# MainPower.net
KiCad netlist of a schematic drawn in Altium Designer
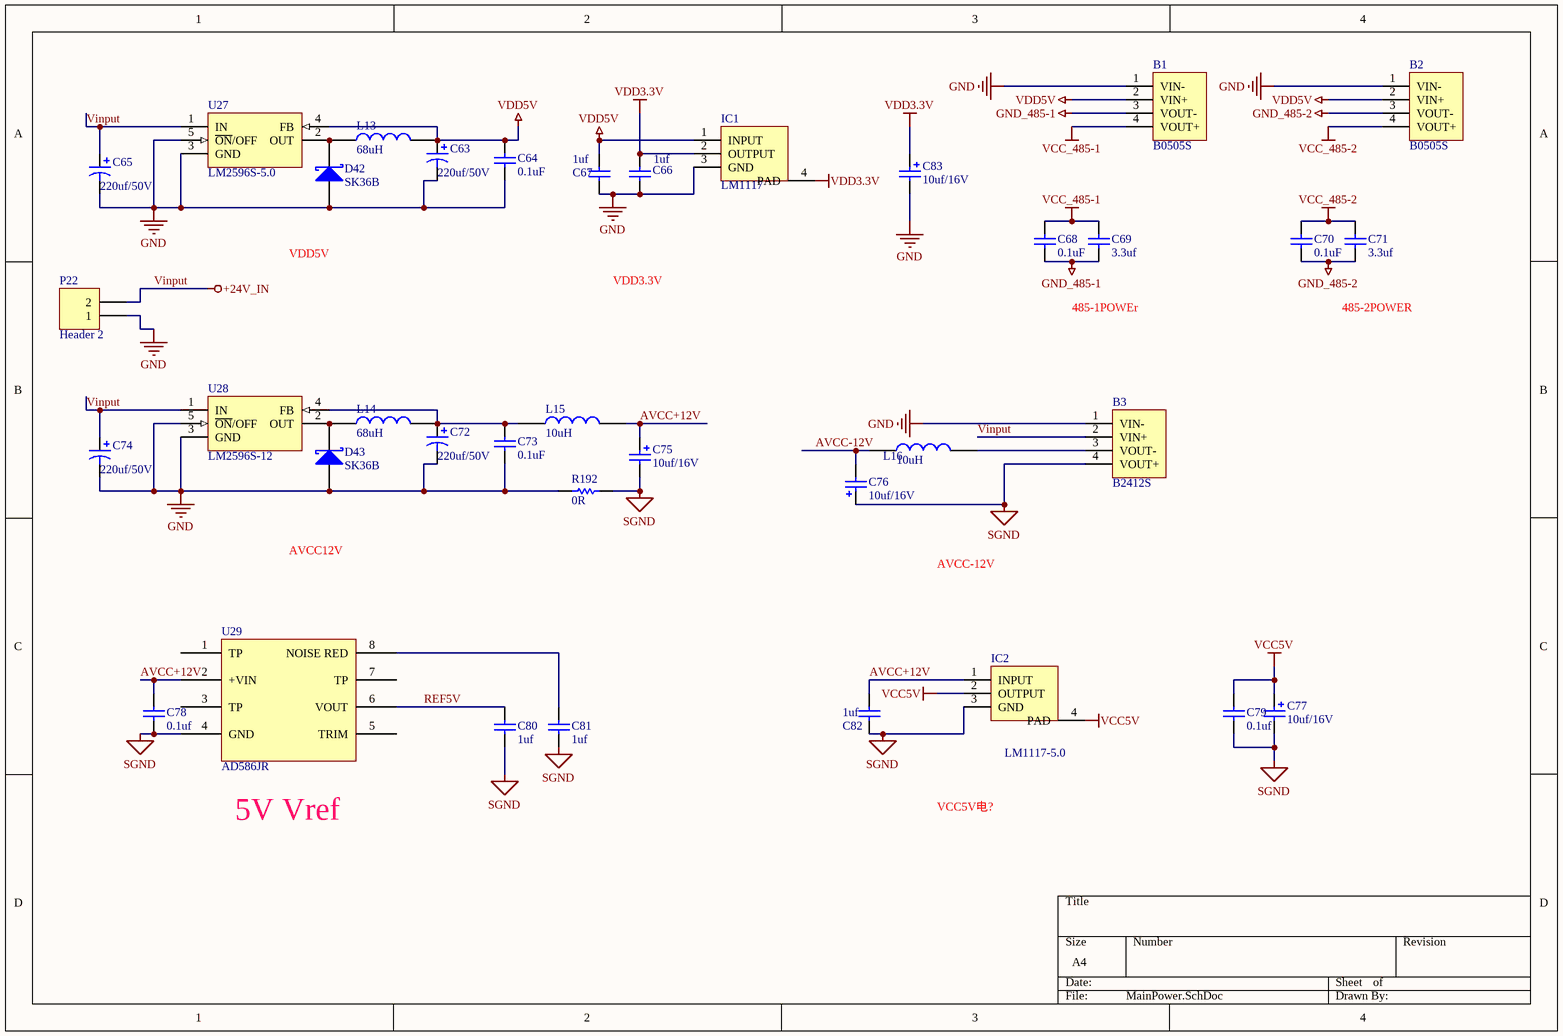
[diagram p0: MainPower.SchDoc]

(export (version "E")
  (design (tool "Eeschema 10.0.6"))
  (components
    (comp (ref "B1") (value "B0505S") (footprint "B0505S") (libsource (lib "S1") (part "B0505S")))
    (comp (ref "B2") (value "B0505S") (footprint "B0505S") (libsource (lib "S1") (part "B0505S")))
    (comp (ref "B3") (value "B2412S") (footprint "B0505S") (libsource (lib "S1") (part "B0505S")))
    (comp (ref "C63")
      (value "220uf/50V")
      (footprint "Cap5*10*12")
      (description "Polarized Capacitor (Radial)")
      (fields (field (name "Comment") "Cap Pol1") (field (name "PUBLISHER") "Altium Limited"))
      (libsource (lib "Miscellaneous Devices") (part "Cap Pol1"))
    )
    (comp (ref "C64")
      (value "0.1uF")
      (footprint "C0805")
      (description "Capacitor")
      (fields (field (name "Comment") "Cap") (field (name "PUBLISHER") "Altium Limited"))
      (libsource (lib "main board") (part "Cap_2"))
    )
    (comp (ref "C65")
      (value "220uf/50V")
      (footprint "Cap5*10*12")
      (description "Polarized Capacitor (Radial)")
      (fields (field (name "Comment") "Cap Pol1") (field (name "PUBLISHER") "Altium Limited"))
      (libsource (lib "Miscellaneous Devices") (part "Cap Pol1"))
    )
    (comp (ref "C66")
      (value "1uf")
      (footprint "C0805")
      (description "Capacitor")
      (fields
        (field (name "MANUFACTURER") "Generic Components")
        (field (name "Comment") "Cap")
        (field (name "PUBLISHER") "Altium Hobart Technology Centre")
      )
      (libsource (lib "Miscellaneous Devices") (part "Cap"))
    )
    (comp (ref "C67")
      (value "1uf")
      (footprint "C0805")
      (description "Capacitor")
      (fields
        (field (name "MANUFACTURER") "Generic Components")
        (field (name "Comment") "Cap")
        (field (name "PUBLISHER") "Altium Hobart Technology Centre")
      )
      (libsource (lib "Miscellaneous Devices") (part "Cap"))
    )
    (comp (ref "C68")
      (value "0.1uF")
      (footprint "C0805")
      (description "Capacitor")
      (fields (field (name "Comment") "Cap") (field (name "PUBLISHER") "Altium Limited"))
      (libsource (lib "main board") (part "Cap_2"))
    )
    (comp (ref "C69")
      (value "3.3uf")
      (footprint "C0805")
      (description "Capacitor")
      (fields (field (name "Comment") "Cap") (field (name "PUBLISHER") "Altium Limited"))
      (libsource (lib "main board") (part "Cap_2"))
    )
    (comp (ref "C70")
      (value "0.1uF")
      (footprint "C0805")
      (description "Capacitor")
      (fields (field (name "Comment") "Cap") (field (name "PUBLISHER") "Altium Limited"))
      (libsource (lib "main board") (part "Cap_2"))
    )
    (comp (ref "C71")
      (value "3.3uf")
      (footprint "C0805")
      (description "Capacitor")
      (fields (field (name "Comment") "Cap") (field (name "PUBLISHER") "Altium Limited"))
      (libsource (lib "main board") (part "Cap_2"))
    )
    (comp (ref "C72")
      (value "220uf/50V")
      (footprint "Cap5*10*12")
      (description "Polarized Capacitor (Radial)")
      (fields (field (name "Comment") "Cap Pol1") (field (name "PUBLISHER") "Altium Limited"))
      (libsource (lib "Miscellaneous Devices") (part "Cap Pol1"))
    )
    (comp (ref "C73")
      (value "0.1uF")
      (footprint "C0805")
      (description "Capacitor")
      (fields (field (name "Comment") "Cap") (field (name "PUBLISHER") "Altium Limited"))
      (libsource (lib "main board") (part "Cap_2"))
    )
    (comp (ref "C74")
      (value "220uf/50V")
      (footprint "Cap5*10*12")
      (description "Polarized Capacitor (Radial)")
      (fields (field (name "Comment") "Cap Pol1") (field (name "PUBLISHER") "Altium Limited"))
      (libsource (lib "Miscellaneous Devices") (part "Cap Pol1"))
    )
    (comp (ref "C75")
      (value "10uf/16V")
      (footprint "Cap-A")
      (description "Polarized Capacitor (Axial)")
      (fields (field (name "PUBLISHER") "Altium Limited"))
      (libsource (lib "Miscellaneous Devices") (part "Cap Pol2"))
    )
    (comp (ref "C76")
      (value "10uf/16V")
      (footprint "Cap-A")
      (description "Polarized Capacitor (Axial)")
      (fields (field (name "PUBLISHER") "Altium Limited"))
      (libsource (lib "Miscellaneous Devices") (part "Cap Pol2"))
    )
    (comp (ref "C77")
      (value "10uf/16V")
      (footprint "Cap-A")
      (description "Polarized Capacitor (Axial)")
      (fields (field (name "PUBLISHER") "Altium Limited"))
      (libsource (lib "Miscellaneous Devices") (part "Cap Pol2"))
    )
    (comp (ref "C78")
      (value "0.1uf")
      (footprint "C0805")
      (description "Capacitor")
      (fields
        (field (name "MANUFACTURER") "Generic Components")
        (field (name "Comment") "Cap")
        (field (name "PUBLISHER") "Altium Hobart Technology Centre")
      )
      (libsource (lib "Miscellaneous Devices") (part "Cap"))
    )
    (comp (ref "C79")
      (value "0.1uf")
      (footprint "C0805")
      (description "Capacitor")
      (fields
        (field (name "MANUFACTURER") "Generic Components")
        (field (name "Comment") "Cap")
        (field (name "PUBLISHER") "Altium Hobart Technology Centre")
      )
      (libsource (lib "Miscellaneous Devices") (part "Cap"))
    )
    (comp (ref "C80")
      (value "1uf")
      (footprint "C0805")
      (description "Capacitor")
      (fields
        (field (name "MANUFACTURER") "Generic Components")
        (field (name "Comment") "Cap")
        (field (name "PUBLISHER") "Altium Hobart Technology Centre")
      )
      (libsource (lib "Miscellaneous Devices") (part "Cap"))
    )
    (comp (ref "C81")
      (value "1uf")
      (footprint "C0805")
      (description "Capacitor")
      (fields
        (field (name "MANUFACTURER") "Generic Components")
        (field (name "Comment") "Cap")
        (field (name "PUBLISHER") "Altium Hobart Technology Centre")
      )
      (libsource (lib "Miscellaneous Devices") (part "Cap"))
    )
    (comp (ref "C82")
      (value "1uf")
      (footprint "C0805")
      (description "Capacitor")
      (fields
        (field (name "MANUFACTURER") "Generic Components")
        (field (name "Comment") "Cap")
        (field (name "PUBLISHER") "Altium Hobart Technology Centre")
      )
      (libsource (lib "Miscellaneous Devices") (part "Cap"))
    )
    (comp (ref "C83")
      (value "10uf/16V")
      (footprint "Cap-A")
      (description "Polarized Capacitor (Axial)")
      (fields (field (name "PUBLISHER") "Altium Limited"))
      (libsource (lib "Miscellaneous Devices") (part "Cap Pol2"))
    )
    (comp (ref "D42")
      (value "SK36B")
      (footprint "SMB")
      (description "Schottky Diode")
      (fields (field (name "PUBLISHER") "Altium Limited"))
      (libsource (lib "Miscellaneous Devices") (part "D Schottky"))
    )
    (comp (ref "D43")
      (value "SK36B")
      (footprint "SMB")
      (description "Schottky Diode")
      (fields (field (name "PUBLISHER") "Altium Limited"))
      (libsource (lib "Miscellaneous Devices") (part "D Schottky"))
    )
    (comp (ref "IC1") (value "LM1117") (footprint "LM1117") (libsource (lib "S1") (part "LM1117")))
    (comp (ref "IC2") (value "LM1117-5.0") (footprint "LM1117") (libsource (lib "S1") (part "LM1117")))
    (comp (ref "L13") (value "68uH") (footprint "IND_HM00_12*12") (libsource (lib "电源板") (part "INDUCTOR")))
    (comp (ref "L14") (value "68uH") (footprint "IND_HM00_12*12") (libsource (lib "电源板") (part "INDUCTOR")))
    (comp (ref "L15") (value "10uH") (footprint "L1206") (libsource (lib "电源板") (part "INDUCTOR")))
    (comp (ref "L16") (value "10uH") (footprint "L1206") (libsource (lib "电源板") (part "INDUCTOR")))
    (comp (ref "P22")
      (value "Header 2")
      (footprint "JIEKE_2PX508")
      (description "Header, 2-Pin")
      (fields (field (name "PUBLISHER") "Altium Limited"))
      (libsource (lib "Miscellaneous Connectors") (part "Header 2"))
    )
    (comp (ref "R192")
      (value "0R")
      (footprint "0805")
      (description "Semiconductor Resistor")
      (fields (field (name "Comment") "Res Semi") (field (name "PUBLISHER") "Altium Limited"))
      (libsource (lib "Miscellaneous Devices") (part "Res Semi"))
    )
    (comp (ref "U27")
      (value "LM2596S-5.0")
      (footprint "TS5B_M")
      (description "Simple Switcher Power Converter 150 kHz 3A Step Down Voltage Regulator")
      (fields (field (name "PUBLISHER") "Altium Limited"))
      (libsource (lib "NSC Power Mgt Switching Regulator") (part "LM2596S-5.0"))
    )
    (comp (ref "U28")
      (value "LM2596S-12")
      (footprint "TS5B_M")
      (description "Simple Switcher Power Converter 150 kHz 3A Step Down Voltage Regulator")
      (fields (field (name "PUBLISHER") "Altium Limited"))
      (libsource (lib "NSC Power Mgt Switching Regulator") (part "LM2596S-12"))
    )
    (comp (ref "U29") (value "AD586JR") (footprint "SOP8_M") (libsource (lib "斜测仪") (part "AD586L")))
  )
  (nets
    (net (code "1") (name "+24V_IN") (class "Default")
      (node (ref "B3") (pin "2") (pinfunction "VIN+_2") (pintype "passive"))
      (node (ref "C65") (pin "1") (pinfunction "1_1") (pintype "passive"))
      (node (ref "C74") (pin "1") (pinfunction "1_1") (pintype "passive"))
      (node (ref "P22") (pin "2") (pinfunction "2_2") (pintype "passive"))
      (node (ref "U27") (pin "1") (pinfunction "IN_1") (pintype "power_in"))
      (node (ref "U28") (pin "1") (pinfunction "IN_1") (pintype "power_in"))
    )
    (net (code "2") (name "/AVCC+12V") (class "Default")
      (node (ref "C75") (pin "1") (pinfunction "1_1") (pintype "passive"))
      (node (ref "C78") (pin "1") (pinfunction "1_1") (pintype "passive"))
      (node (ref "C82") (pin "1") (pinfunction "1_1") (pintype "passive"))
      (node (ref "IC2") (pin "1") (pinfunction "INPUT_1") (pintype "passive"))
      (node (ref "L15") (pin "2") (pinfunction "2_2") (pintype "passive"))
      (node (ref "U29") (pin "2") (pinfunction "+VIN_2") (pintype "passive"))
    )
    (net (code "3") (name "/AVCC-12V") (class "Default")
      (node (ref "C76") (pin "2") (pinfunction "2_2") (pintype "passive"))
      (node (ref "L16") (pin "1") (pinfunction "1_1") (pintype "passive"))
    )
    (net (code "4") (name "/REF5V") (class "Default")
      (node (ref "C80") (pin "1") (pinfunction "1_1") (pintype "passive"))
      (node (ref "U29") (pin "6") (pinfunction "VOUT_6") (pintype "passive"))
    )
    (net (code "5") (name "GND") (class "Default")
      (node (ref "B1") (pin "1") (pinfunction "VIN-_1") (pintype "passive"))
      (node (ref "B2") (pin "1") (pinfunction "VIN-_1") (pintype "passive"))
      (node (ref "B3") (pin "1") (pinfunction "VIN-_1") (pintype "passive"))
      (node (ref "C63") (pin "2") (pinfunction "2_2") (pintype "passive"))
      (node (ref "C64") (pin "1") (pinfunction "1_1") (pintype "passive"))
      (node (ref "C65") (pin "2") (pinfunction "2_2") (pintype "passive"))
      (node (ref "C66") (pin "2") (pinfunction "2_2") (pintype "passive"))
      (node (ref "C67") (pin "2") (pinfunction "2_2") (pintype "passive"))
      (node (ref "C72") (pin "2") (pinfunction "2_2") (pintype "passive"))
      (node (ref "C73") (pin "1") (pinfunction "1_1") (pintype "passive"))
      (node (ref "C74") (pin "2") (pinfunction "2_2") (pintype "passive"))
      (node (ref "C83") (pin "2") (pinfunction "2_2") (pintype "passive"))
      (node (ref "D42") (pin "1") (pinfunction "A_1") (pintype "passive"))
      (node (ref "D43") (pin "1") (pinfunction "A_1") (pintype "passive"))
      (node (ref "IC1") (pin "3") (pinfunction "GND_3") (pintype "passive"))
      (node (ref "P22") (pin "1") (pinfunction "1_1") (pintype "passive"))
      (node (ref "R192") (pin "2") (pinfunction "2_2") (pintype "passive"))
      (node (ref "U27") (pin "3") (pinfunction "GND_3") (pintype "power_in"))
      (node (ref "U27") (pin "5") (pinfunction "~{ON}/OFF_5") (pintype "input"))
      (node (ref "U28") (pin "3") (pinfunction "GND_3") (pintype "power_in"))
      (node (ref "U28") (pin "5") (pinfunction "~{ON}/OFF_5") (pintype "input"))
    )
    (net (code "6") (name "GND_485-1") (class "Default")
      (node (ref "B1") (pin "3") (pinfunction "VOUT-_3") (pintype "passive"))
      (node (ref "C68") (pin "1") (pinfunction "1_1") (pintype "passive"))
      (node (ref "C69") (pin "1") (pinfunction "1_1") (pintype "passive"))
    )
    (net (code "7") (name "GND_485-2") (class "Default")
      (node (ref "B2") (pin "3") (pinfunction "VOUT-_3") (pintype "passive"))
      (node (ref "C70") (pin "1") (pinfunction "1_1") (pintype "passive"))
      (node (ref "C71") (pin "1") (pinfunction "1_1") (pintype "passive"))
    )
    (net (code "8") (name "Net-(B3-VOUT-)") (class "Default")
      (node (ref "B3") (pin "3") (pinfunction "VOUT-_3") (pintype "passive"))
      (node (ref "L16") (pin "2") (pinfunction "2_2") (pintype "passive"))
    )
    (net (code "9") (name "Net-(D42-K)") (class "Default")
      (node (ref "D42") (pin "2") (pinfunction "K_2") (pintype "passive"))
      (node (ref "L13") (pin "1") (pinfunction "1_1") (pintype "passive"))
      (node (ref "U27") (pin "2") (pinfunction "OUT_2") (pintype "power_in"))
    )
    (net (code "10") (name "Net-(D43-K)") (class "Default")
      (node (ref "D43") (pin "2") (pinfunction "K_2") (pintype "passive"))
      (node (ref "L14") (pin "1") (pinfunction "1_1") (pintype "passive"))
      (node (ref "U28") (pin "2") (pinfunction "OUT_2") (pintype "power_in"))
    )
    (net (code "11") (name "Net-(U28-FB)") (class "Default")
      (node (ref "C72") (pin "1") (pinfunction "1_1") (pintype "passive"))
      (node (ref "C73") (pin "2") (pinfunction "2_2") (pintype "passive"))
      (node (ref "L14") (pin "2") (pinfunction "2_2") (pintype "passive"))
      (node (ref "L15") (pin "1") (pinfunction "1_1") (pintype "passive"))
      (node (ref "U28") (pin "4") (pinfunction "FB_4") (pintype "input"))
    )
    (net (code "12") (name "Net-(U29-NOISE_RED)") (class "Default")
      (node (ref "C81") (pin "1") (pinfunction "1_1") (pintype "passive"))
      (node (ref "U29") (pin "8") (pinfunction "NOISE_RED_8") (pintype "passive"))
    )
    (net (code "13") (name "SGND") (class "Default")
      (node (ref "B3") (pin "4") (pinfunction "VOUT+_4") (pintype "passive"))
      (node (ref "C75") (pin "2") (pinfunction "2_2") (pintype "passive"))
      (node (ref "C76") (pin "1") (pinfunction "1_1") (pintype "passive"))
      (node (ref "C77") (pin "2") (pinfunction "2_2") (pintype "passive"))
      (node (ref "C78") (pin "2") (pinfunction "2_2") (pintype "passive"))
      (node (ref "C79") (pin "2") (pinfunction "2_2") (pintype "passive"))
      (node (ref "C80") (pin "2") (pinfunction "2_2") (pintype "passive"))
      (node (ref "C81") (pin "2") (pinfunction "2_2") (pintype "passive"))
      (node (ref "C82") (pin "2") (pinfunction "2_2") (pintype "passive"))
      (node (ref "IC2") (pin "3") (pinfunction "GND_3") (pintype "passive"))
      (node (ref "R192") (pin "1") (pinfunction "1_1") (pintype "passive"))
      (node (ref "U29") (pin "4") (pinfunction "GND_4") (pintype "passive"))
    )
    (net (code "14") (name "VCC5V") (class "Default")
      (node (ref "C77") (pin "1") (pinfunction "1_1") (pintype "passive"))
      (node (ref "C79") (pin "1") (pinfunction "1_1") (pintype "passive"))
      (node (ref "IC2") (pin "2") (pinfunction "OUTPUT_2") (pintype "passive"))
      (node (ref "IC2") (pin "4") (pinfunction "PAD_4") (pintype "passive"))
    )
    (net (code "15") (name "VCC_485-1") (class "Default")
      (node (ref "B1") (pin "4") (pinfunction "VOUT+_4") (pintype "passive"))
      (node (ref "C68") (pin "2") (pinfunction "2_2") (pintype "passive"))
      (node (ref "C69") (pin "2") (pinfunction "2_2") (pintype "passive"))
    )
    (net (code "16") (name "VCC_485-2") (class "Default")
      (node (ref "B2") (pin "4") (pinfunction "VOUT+_4") (pintype "passive"))
      (node (ref "C70") (pin "2") (pinfunction "2_2") (pintype "passive"))
      (node (ref "C71") (pin "2") (pinfunction "2_2") (pintype "passive"))
    )
    (net (code "17") (name "VDD3.3V") (class "Default")
      (node (ref "C66") (pin "1") (pinfunction "1_1") (pintype "passive"))
      (node (ref "C83") (pin "1") (pinfunction "1_1") (pintype "passive"))
      (node (ref "IC1") (pin "2") (pinfunction "OUTPUT_2") (pintype "passive"))
      (node (ref "IC1") (pin "4") (pinfunction "PAD_4") (pintype "passive"))
    )
    (net (code "18") (name "VDD5V") (class "Default")
      (node (ref "B1") (pin "2") (pinfunction "VIN+_2") (pintype "passive"))
      (node (ref "B2") (pin "2") (pinfunction "VIN+_2") (pintype "passive"))
      (node (ref "C63") (pin "1") (pinfunction "1_1") (pintype "passive"))
      (node (ref "C64") (pin "2") (pinfunction "2_2") (pintype "passive"))
      (node (ref "C67") (pin "1") (pinfunction "1_1") (pintype "passive"))
      (node (ref "IC1") (pin "1") (pinfunction "INPUT_1") (pintype "passive"))
      (node (ref "L13") (pin "2") (pinfunction "2_2") (pintype "passive"))
      (node (ref "U27") (pin "4") (pinfunction "FB_4") (pintype "input"))
    )
    (net (code "19") (name "unconnected-(U29-TP-Pad1)") (class "Default")
      (node (ref "U29") (pin "1") (pinfunction "TP_1") (pintype "passive"))
    )
    (net (code "20") (name "unconnected-(U29-TP-Pad3)") (class "Default")
      (node (ref "U29") (pin "3") (pinfunction "TP_3") (pintype "passive"))
    )
    (net (code "21") (name "unconnected-(U29-TP-Pad7)") (class "Default")
      (node (ref "U29") (pin "7") (pinfunction "TP_7") (pintype "passive"))
    )
    (net (code "22") (name "unconnected-(U29-TRIM-Pad5)") (class "Default")
      (node (ref "U29") (pin "5") (pinfunction "TRIM_5") (pintype "passive"))
    )
  )
)
